# SUBBOARD-aux_supply.net
KiCad netlist of a schematic drawn in Altium Designer
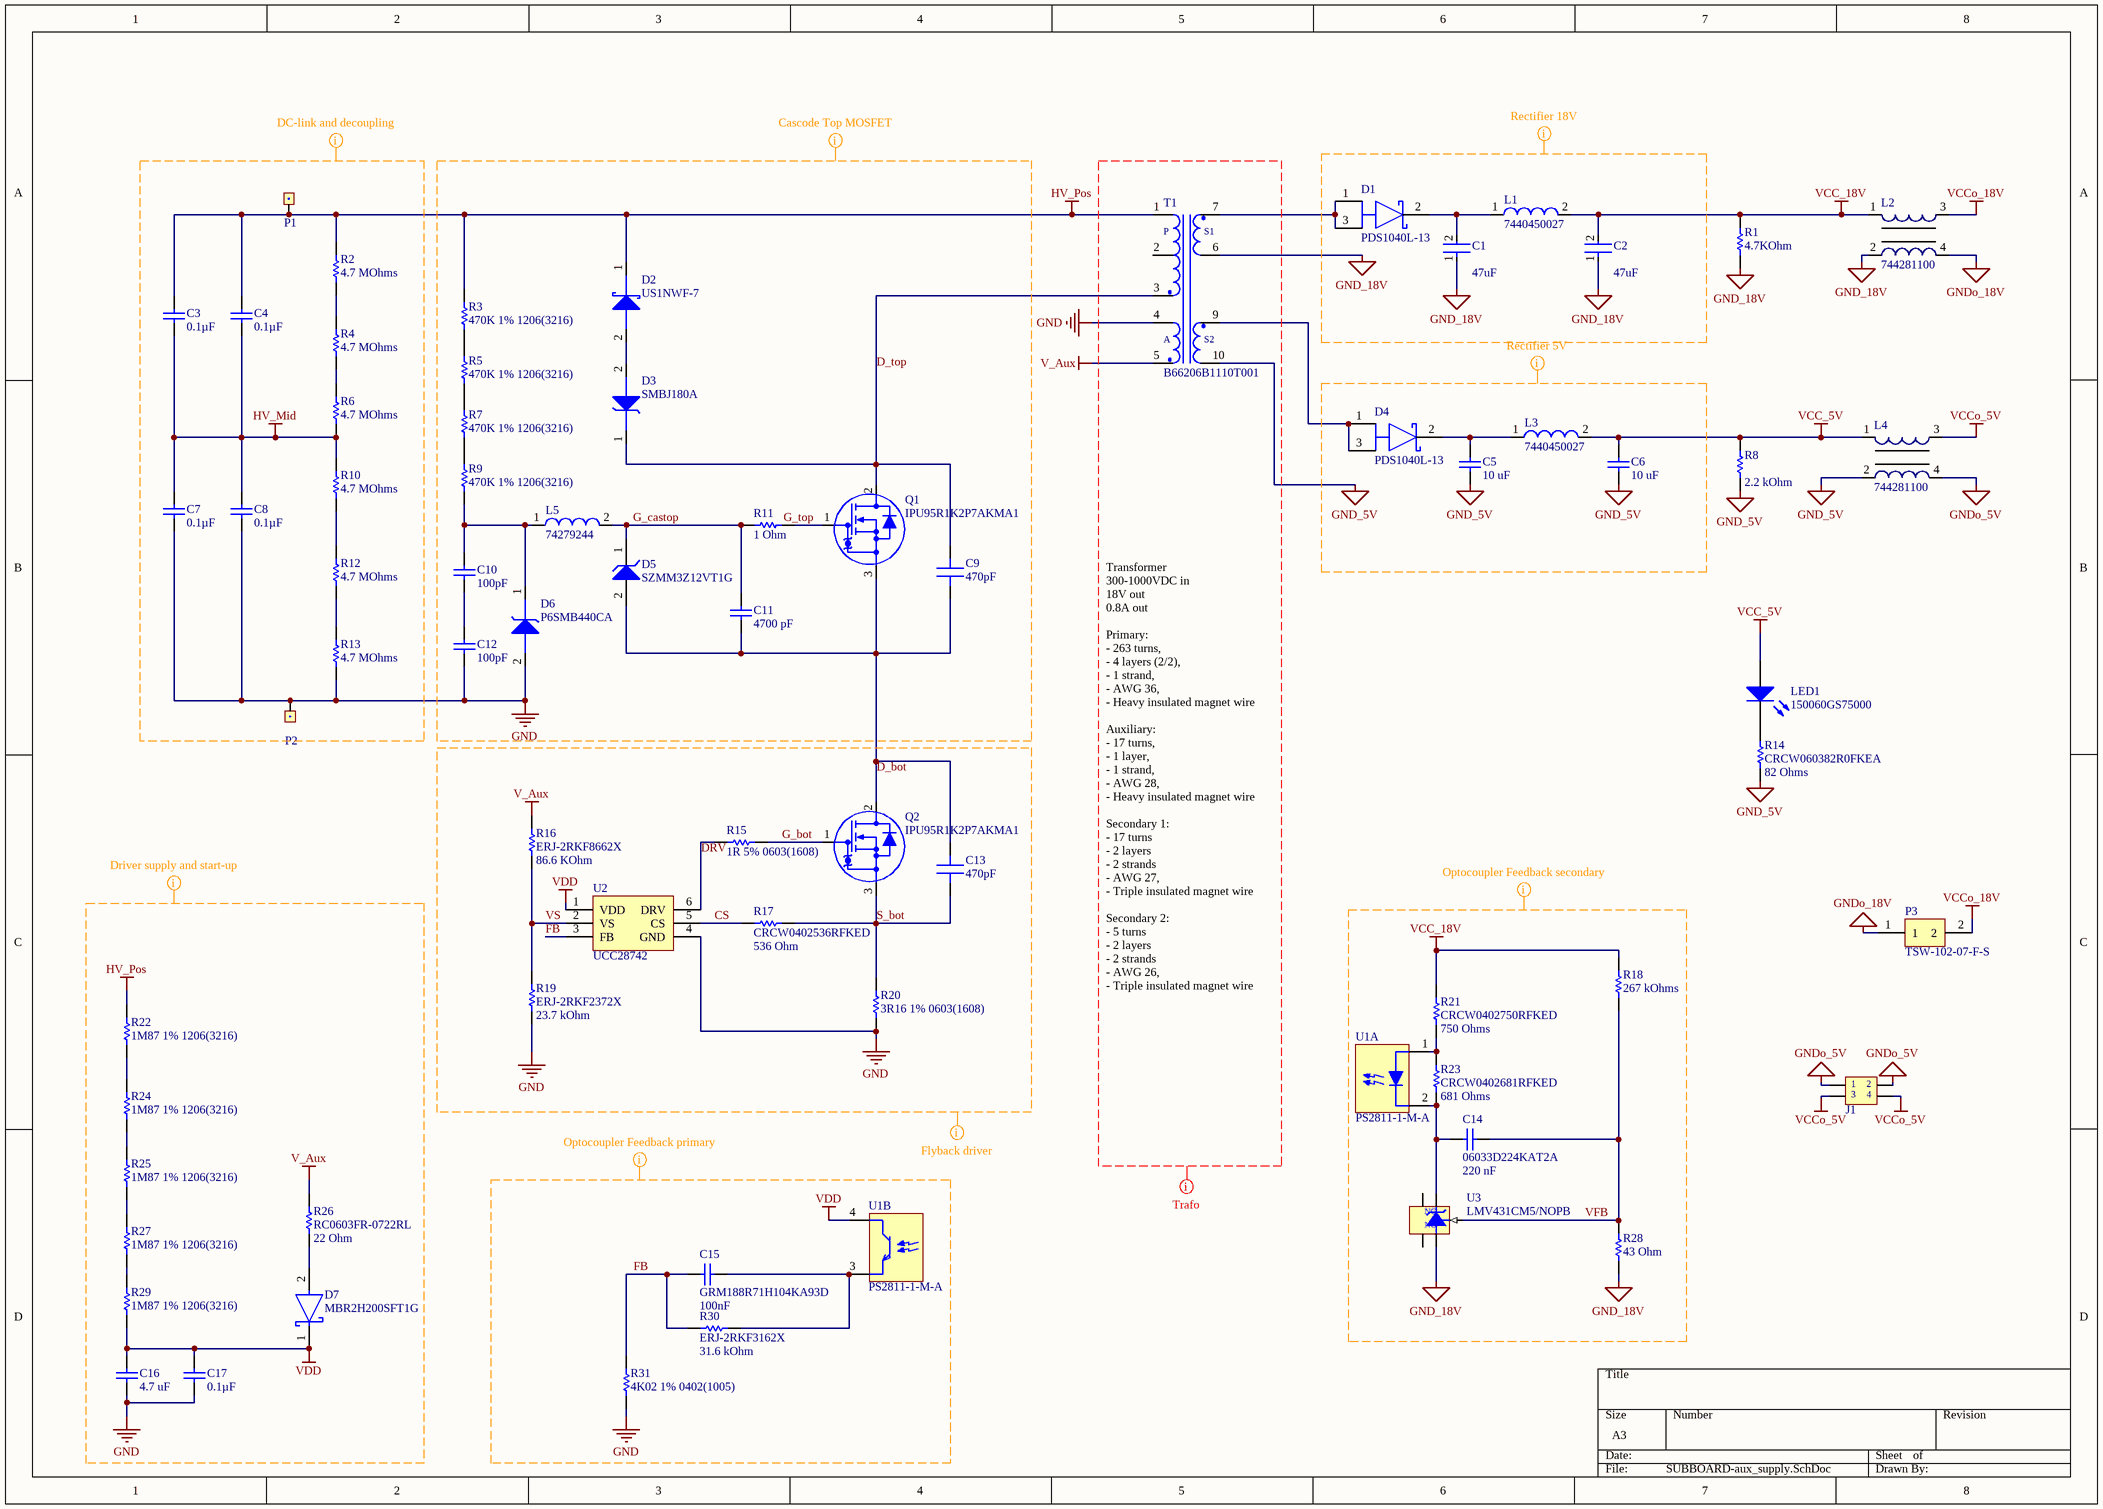
[diagram p0: SUBBOARD-aux_supply.SchDoc]

(export (version "E")
  (design (tool "Eeschema 10.0.6"))
  (components
    (comp (ref "C1")
      (value "47uF")
      (footprint "FP-C3216-160-MFG")
      (description "CAP CER 47UF 25V X5R 1206")
      (fields (field (name "3DS PART NUMBER") "220-00004") (field (name "VOLTAGE") "25V"))
      (libsource (lib "Altium Content Vault") (part "11868f565c42a9108669ba33697ecf6"))
    )
    (comp (ref "C2")
      (value "47uF")
      (footprint "FP-C3216-160-MFG")
      (description "CAP CER 47UF 25V X5R 1206")
      (fields (field (name "3DS PART NUMBER") "220-00004") (field (name "VOLTAGE") "25V"))
      (libsource (lib "Altium Content Vault") (part "11868f565c42a9108669ba33697ecf6"))
    )
    (comp (ref "C3")
      (value "VJ1812Y104KXEAT5Z")
      (footprint "VISH-VJ1812-2_L")
      (fields
        (field (name "MANUFACTURER") "Vishay")
        (field (name "CAPACITANCE") "0.1µF")
        (field (name "TOLERANCE") "±10%")
      )
      (libsource (lib "Altium Content Vault") (part "CAP-NP-2"))
    )
    (comp (ref "C4")
      (value "VJ1812Y104KXEAT5Z")
      (footprint "VISH-VJ1812-2_L")
      (fields
        (field (name "MANUFACTURER") "Vishay")
        (field (name "CAPACITANCE") "0.1µF")
        (field (name "TOLERANCE") "±10%")
      )
      (libsource (lib "Altium Content Vault") (part "CAP-NP-2"))
    )
    (comp (ref "C5")
      (value "10 uF")
      (footprint "CAPC2013X140X45NL15T25")
      (fields (field (name "PART NUMBER") "GRM21BR71A106KE51L") (field (name "MANUFACTURER") "Murata"))
      (libsource (lib "Altium Content Vault") (part "CAP"))
    )
    (comp (ref "C6")
      (value "10 uF")
      (footprint "CAPC2013X140X45NL15T25")
      (fields (field (name "PART NUMBER") "GRM21BR71A106KE51L") (field (name "MANUFACTURER") "Murata"))
      (libsource (lib "Altium Content Vault") (part "CAP"))
    )
    (comp (ref "C7")
      (value "VJ1812Y104KXEAT5Z")
      (footprint "VISH-VJ1812-2_L")
      (fields
        (field (name "MANUFACTURER") "Vishay")
        (field (name "CAPACITANCE") "0.1µF")
        (field (name "TOLERANCE") "±10%")
      )
      (libsource (lib "Altium Content Vault") (part "CAP-NP-2"))
    )
    (comp (ref "C8")
      (value "VJ1812Y104KXEAT5Z")
      (footprint "VISH-VJ1812-2_L")
      (fields
        (field (name "MANUFACTURER") "Vishay")
        (field (name "CAPACITANCE") "0.1µF")
        (field (name "TOLERANCE") "±10%")
      )
      (libsource (lib "Altium Content Vault") (part "CAP-NP-2"))
    )
    (comp (ref "C9")
      (value "C4520X7R3A471K130KA")
      (footprint "CAPC1808(4520)215_L")
      (description "CAP CER 470PF 1KV X7R 1808")
      (fields
        (field (name "MANUFACTURER") "TDK")
        (field (name "CAPACITANCE") "470pF")
        (field (name "TOLERANCE") "10%")
      )
      (libsource (lib "Altium_Library_POWERLAB") (part "C4520X7R3A471K130KA"))
    )
    (comp (ref "C10")
      (value "100pF")
      (footprint "CAPC1206(3216)170_L")
      (description "CAP 100pF 500V ±2% 1206 (3216 Metric) Thickness 1.7mm SMD")
      (fields (field (name "TOLERANCE") "Â±2%") (field (name "Comment") "CAP 100pF 500V 1206(3216)"))
      (libsource (lib "Altium Content Vault") (part "CAP"))
    )
    (comp (ref "C11")
      (value "C0805C472J5RACTU")
      (footprint "CAPC2013X110X50LL20T25")
      (fields (field (name "MANUFACTURER") "Kemet") (field (name "CAPACITANCE") "4700 pF"))
      (libsource (lib "Altium Content Vault") (part "CAP"))
    )
    (comp (ref "C12")
      (value "100pF")
      (footprint "CAPC1206(3216)170_L")
      (description "CAP 100pF 500V ±2% 1206 (3216 Metric) Thickness 1.7mm SMD")
      (fields (field (name "TOLERANCE") "Â±2%") (field (name "Comment") "CAP 100pF 500V 1206(3216)"))
      (libsource (lib "Altium Content Vault") (part "CAP"))
    )
    (comp (ref "C13")
      (value "C4520X7R3A471K130KA")
      (footprint "CAPC1808(4520)215_L")
      (description "CAP CER 470PF 1KV X7R 1808")
      (fields
        (field (name "MANUFACTURER") "TDK")
        (field (name "CAPACITANCE") "470pF")
        (field (name "TOLERANCE") "10%")
      )
      (libsource (lib "Altium_Library_POWERLAB") (part "C4520X7R3A471K130KA"))
    )
    (comp (ref "C14")
      (value "06033D224KAT2A")
      (footprint "CAPC1608X90X35NL15T15")
      (fields (field (name "MANUFACTURER") "AVX Interconnect / Elco") (field (name "CAPACITANCE") "220 nF"))
      (libsource (lib "Altium Content Vault") (part "CAP"))
    )
    (comp (ref "C15")
      (value "GRM188R71H104KA93D")
      (footprint "CAPC1608X90X35LL10T15")
      (description "Chip Capacitor, 0.1 uF, +/- 10%, 50 V, -55 to 125 degC, 0603 (1608 Metric), RoHS, Tape and Reel")
      (fields
        (field (name "TOLERANCE") "10%")
        (field (name "CAPACITANCE") "100nF")
        (field (name "VOLTAGE") "50V")
      )
      (libsource (lib "Altium Content Vault") (part "CAP-NP-2"))
    )
    (comp (ref "C16")
      (value "GRM219R6YA475MA73D")
      (footprint "CAPC2013X95X45NL15T25")
      (fields (field (name "MANUFACTURER") "Murata") (field (name "CAPACITANCE") "4.7 uF"))
      (libsource (lib "Altium Content Vault") (part "CAP"))
    )
    (comp (ref "C17")
      (value "CL10B104KB8NNNC")
      (footprint "SAMS-C0603-2_L")
      (description "Multi-layer Ceramic Capacitor, -55 to 125 degC, 2-Pin SMD (0603), RoHS, Tape and Reel")
      (fields (field (name "CAPACITANCE") "0.1µF") (field (name "MANUFACTURER") "Samsung Electro-Mechanics"))
      (libsource (lib "Altium Content Vault") (part "CAP-NP-2"))
    )
    (comp (ref "D1")
      (value "PDS1040L-13")
      (footprint "FP-PowerDI5-MFG")
      (description "DIODE SCHOTTKY 40V 10A POWERDI5")
      (fields
        (field (name "OCTOPART") "https://octopart.com/pds1040l-13-diodes+inc.-332540")
        (field (name "MANUFACTURER") "Diodes Inc.")
      )
      (libsource (lib "Altium Content Vault") (part "742f7ab95c42997246ebbe41a6c66ae"))
    )
    (comp (ref "D2")
      (value "US1NWF-7")
      (footprint "SOD123F")
      (description "DIODE GEN PURP 1.2KV 1A SOD123F")
      (fields (field (name "MANUFACTURER") "Diodes"))
      (libsource (lib "Altium_Library_POWERLAB") (part "US1NWF-7"))
    )
    (comp (ref "D3")
      (value "SMBJ180A")
      (footprint "DO-214AA SMB")
      (description "Diode TVS Single Uni-Dir 180V 600W 2-Pin SMB T/R")
      (fields (field (name "MANUFACTURER") "Littelfuse"))
      (libsource (lib "Altium_Library_POWERLAB") (part "SMBJ180A"))
    )
    (comp (ref "D4")
      (value "PDS1040L-13")
      (footprint "FP-PowerDI5-MFG")
      (description "DIODE SCHOTTKY 40V 10A POWERDI5")
      (fields
        (field (name "OCTOPART") "https://octopart.com/pds1040l-13-diodes+inc.-332540")
        (field (name "MANUFACTURER") "Diodes Inc.")
      )
      (libsource (lib "Altium Content Vault") (part "742f7ab95c42997246ebbe41a6c66ae"))
    )
    (comp (ref "D5")
      (value "SZMM3Z12VT1G")
      (footprint "ONSC-SOD-323-2-477-02_V")
      (description "Zener Voltage Regulator, 300 mW, 2-Pin SOD-323, Pb-Free, Tape and Reel")
      (fields (field (name "MANUFACTURER") "On Semiconductor"))
      (libsource (lib "Altium Content Vault") (part "ONSC-K1A2-2"))
    )
    (comp (ref "D6")
      (value "P6SMB440CA")
      (footprint "DO-214AA SMB")
      (description "LITTELFUSE - P6SMB440CA - TVS Diode, P6SMB series, Bidirectional, 376 V, 602 V, DO-214AA, 2 Pins")
      (fields (field (name "MANUFACTURER") "Littelfuse"))
      (libsource (lib "Altium_Library_POWERLAB") (part "P6SMB440CA"))
    )
    (comp (ref "D7")
      (value "MBR2H200SFT1G")
      (footprint "FP-498-MFG")
      (description "DIODE SCHOTTKY 200V 2A SOD123FL")
      (fields
        (field (name "MANUFACTURER") "ON Semiconductor")
        (field (name "OCTOPART") "https://octopart.com/mbr2h200sft1g-on+semiconductor-51167333")
      )
      (libsource (lib "Altium Content Vault") (part "1d6ec82d83fb6aee721767c19dac4b9"))
    )
    (comp (ref "J1")
      (value "SQT-102-01-F-D")
      (footprint "SQT-102-01-F-D")
      (description "Conn Socket Strip SKT 4 POS 2mm Solder ST Thru-Hole")
      (fields (field (name "MANUFACTURER") "Samtec"))
      (libsource (lib "Altium_Library_POWERLAB") (part "SQT-102-01-F-D"))
    )
    (comp (ref "L1")
      (value "7440450027")
      (footprint "WE-LQ-L")
      (description "SMD-RF-Inductor WE-LQ, L = 2.70 µH")
      (libsource (lib "Altium Content Vault") (part "PAS-IND-INDUCTOR-2"))
    )
    (comp (ref "L2")
      (value "744281100")
      (footprint "WE-SCC 7345")
      (description "SMD Common Mode Line Filter WE-SCC, L=10.0 µH")
      (fields (field (name "MANUFACTURER") "Wuerth Elektronik"))
      (libsource (lib "Altium Content Vault") (part "WE-IND-INDUCTOR-4E"))
    )
    (comp (ref "L3")
      (value "7440450027")
      (footprint "WE-LQ-L")
      (description "SMD-RF-Inductor WE-LQ, L = 2.70 µH")
      (libsource (lib "Altium Content Vault") (part "PAS-IND-INDUCTOR-2"))
    )
    (comp (ref "L4")
      (value "744281100")
      (footprint "WE-SCC 7345")
      (description "SMD Common Mode Line Filter WE-SCC, L=10.0 µH")
      (fields (field (name "MANUFACTURER") "Wuerth Elektronik"))
      (libsource (lib "Altium Content Vault") (part "WE-IND-INDUCTOR-4E"))
    )
    (comp (ref "L5")
      (value "74279244")
      (footprint "SMD-1806")
      (description "SMD EMI Suppression Ferrite Bead WE-CBF, Z = 850 Ohm")
      (libsource (lib "Altium Content Vault") (part "PAS-IND-INDUCTOR-2"))
    )
    (comp (ref "LED1")
      (value "150060GS75000")
      (footprint "0603_A")
      (description "SMD mono-color Chip LED, WL-SMCW, Green")
      (fields (field (name "MANUFACTURER") "Wuerth Elektronik"))
      (libsource (lib "Altium Content Vault") (part "WE-LED_K1A2-2"))
    )
    (comp (ref "P1")
      (value "TSW-101-07-F-S")
      (footprint "TSW-101-07-F-S")
      (description "In a Pack of 50, Samtec TSW, 1 Way, 1 Row, Straight PCB Header")
      (fields (field (name "MANUFACTURER") "Samtec"))
      (libsource (lib "") (part "TSW-101-07-F-S_1"))
    )
    (comp (ref "P2")
      (value "TSW-101-07-F-S")
      (footprint "TSW-101-07-F-S")
      (description "In a Pack of 50, Samtec TSW, 1 Way, 1 Row, Straight PCB Header")
      (fields (field (name "MANUFACTURER") "Samtec"))
      (libsource (lib "Altium_Library_POWERLAB") (part "TSW-101-07-F-S"))
    )
    (comp (ref "P3")
      (value "TSW-102-07-F-S")
      (footprint "TSW-102-07-F-S")
      (description "Conn Unshrouded Header HDR 2 POS 2.54mm Solder ST Thru-Hole")
      (fields (field (name "MANUFACTURER") "Samtec"))
      (libsource (lib "Altium_Library_POWERLAB") (part "TSW-102-07-F-S"))
    )
    (comp (ref "Q1")
      (value "IPU95R1K2P7AKMA1")
      (footprint "IPAK")
      (description "Trans MOSFET N-CH 600V 6A 3-Pin(3+Tab) TO-251 Tube")
      (fields (field (name "MANUFACTURER") "Infineon"))
      (libsource (lib "Altium_Library_POWERLAB") (part "IPU95R1K2P7AKMA1"))
    )
    (comp (ref "Q2")
      (value "IPU95R1K2P7AKMA1")
      (footprint "IPAK")
      (description "Trans MOSFET N-CH 600V 6A 3-Pin(3+Tab) TO-251 Tube")
      (fields (field (name "MANUFACTURER") "Infineon"))
      (libsource (lib "Altium_Library_POWERLAB") (part "IPU95R1K2P7AKMA1"))
    )
    (comp (ref "R1")
      (value "CRCW12064K70FKEA")
      (footprint "RESC3216X60X45LL15T20")
      (description "Chip Resistor, 4.7 KOhm, +/- 1%, 0.25 W, -55 to 155 degC, 1206 (3216 Metric), RoHS, Tape and Reel")
      (fields
        (field (name "MANUFACTURER") "Vishay Semiconductor")
        (field (name "RESISTANCE") "4.7KOhm")
        (field (name "TOLERANCE") "1%")
      )
      (libsource (lib "Altium Content Vault") (part "RES-2"))
    )
    (comp (ref "R2")
      (value "4.7 MOhms")
      (footprint "RESC3216X60X45LL10T20")
      (fields (field (name "MANUFACTURER") "Vishay Dale") (field (name "PART NUMBER") "CRCW12064M70FKEA"))
      (libsource (lib "Altium Content Vault") (part "RES"))
    )
    (comp (ref "R3")
      (value "470K 1% 1206(3216)")
      (footprint "RESC1206(3216)_L")
      (description "470K 0.25W 1% 1206 (3216 Metric)  SMD")
      (fields (field (name "TOLERANCE") "1 %") (field (name "POWER") "0.25 W"))
      (libsource (lib "Altium Content Vault") (part "RES"))
    )
    (comp (ref "R4")
      (value "4.7 MOhms")
      (footprint "RESC3216X60X45LL10T20")
      (fields (field (name "MANUFACTURER") "Vishay Dale") (field (name "PART NUMBER") "CRCW12064M70FKEA"))
      (libsource (lib "Altium Content Vault") (part "RES"))
    )
    (comp (ref "R5")
      (value "470K 1% 1206(3216)")
      (footprint "RESC1206(3216)_L")
      (description "470K 0.25W 1% 1206 (3216 Metric)  SMD")
      (fields (field (name "TOLERANCE") "1 %") (field (name "POWER") "0.25 W"))
      (libsource (lib "Altium Content Vault") (part "RES"))
    )
    (comp (ref "R6")
      (value "4.7 MOhms")
      (footprint "RESC3216X60X45LL10T20")
      (fields (field (name "MANUFACTURER") "Vishay Dale") (field (name "PART NUMBER") "CRCW12064M70FKEA"))
      (libsource (lib "Altium Content Vault") (part "RES"))
    )
    (comp (ref "R7")
      (value "470K 1% 1206(3216)")
      (footprint "RESC1206(3216)_L")
      (description "470K 0.25W 1% 1206 (3216 Metric)  SMD")
      (fields (field (name "TOLERANCE") "1 %") (field (name "POWER") "0.25 W"))
      (libsource (lib "Altium Content Vault") (part "RES"))
    )
    (comp (ref "R8")
      (value "2.2 kOhm")
      (footprint "RESC3216X60X45LL10T20")
      (fields (field (name "MANUFACTURER") "Vishay Dale") (field (name "PART NUMBER") "CRCW12062K20FKEA"))
      (libsource (lib "Altium Content Vault") (part "RES"))
    )
    (comp (ref "R9")
      (value "470K 1% 1206(3216)")
      (footprint "RESC1206(3216)_L")
      (description "470K 0.25W 1% 1206 (3216 Metric)  SMD")
      (fields (field (name "TOLERANCE") "1 %") (field (name "POWER") "0.25 W"))
      (libsource (lib "Altium Content Vault") (part "RES"))
    )
    (comp (ref "R10")
      (value "4.7 MOhms")
      (footprint "RESC3216X60X45LL10T20")
      (fields (field (name "MANUFACTURER") "Vishay Dale") (field (name "PART NUMBER") "CRCW12064M70FKEA"))
      (libsource (lib "Altium Content Vault") (part "RES"))
    )
    (comp (ref "R11")
      (value "1 Ohm")
      (footprint "RESC0603(1608)_L")
      (description "1R 0.1W 5% 0603 (1608 Metric)  SMD")
      (fields (field (name "POWER") "0.1 W") (field (name "TOLERANCE") "5 %"))
      (libsource (lib "Altium Content Vault") (part "RES"))
    )
    (comp (ref "R12")
      (value "4.7 MOhms")
      (footprint "RESC3216X60X45LL10T20")
      (fields (field (name "MANUFACTURER") "Vishay Dale") (field (name "PART NUMBER") "CRCW12064M70FKEA"))
      (libsource (lib "Altium Content Vault") (part "RES"))
    )
    (comp (ref "R13")
      (value "4.7 MOhms")
      (footprint "RESC3216X60X45LL10T20")
      (fields (field (name "MANUFACTURER") "Vishay Dale") (field (name "PART NUMBER") "CRCW12064M70FKEA"))
      (libsource (lib "Altium Content Vault") (part "RES"))
    )
    (comp (ref "R14")
      (value "CRCW060382R0FKEA")
      (footprint "RESC1609X50X30LL10T20")
      (fields (field (name "MANUFACTURER") "Vishay Dale") (field (name "ALTIUM_VALUE") "82 Ohms"))
      (libsource (lib "Altium Content Vault") (part "RES"))
    )
    (comp (ref "R15")
      (value "1R 5% 0603(1608)")
      (footprint "RESC0603(1608)_L")
      (description "1R 0.1W 5% 0603 (1608 Metric)  SMD")
      (fields (field (name "POWER") "0.1 W") (field (name "TOLERANCE") "5 %"))
      (libsource (lib "Altium Content Vault") (part "RES"))
    )
    (comp (ref "R16")
      (value "ERJ-2RKF8662X")
      (footprint "RESC1005X40X25ML05T05")
      (description "Chip Resistor, 86.6 KOhm, +/- 1%, 100 mW, -55 to 155 degC, 0402 (1005 Metric), RoHS, Tape and Reel")
      (fields
        (field (name "TOLERANCE") "1%")
        (field (name "RESISTANCE") "86.6 KOhm")
        (field (name "MANUFACTURER") "Basic Passives")
      )
      (libsource (lib "Altium Content Vault") (part "RES-2"))
    )
    (comp (ref "R17")
      (value "CRCW0402536RFKED")
      (footprint "RESC1005X40X25ML05T05")
      (fields (field (name "MANUFACTURER") "Vishay Dale") (field (name "RESISTANCE") "536 Ohm"))
      (libsource (lib "Altium Content Vault") (part "RES"))
    )
    (comp (ref "R18")
      (value "CRCW0402267KFKED")
      (footprint "RESC1005X40X25NL05T05")
      (fields (field (name "MANUFACTURER") "Vishay Dale") (field (name "RESISTANCE") "267 kOhms"))
      (libsource (lib "Altium Content Vault") (part "RES"))
    )
    (comp (ref "R19")
      (value "ERJ-2RKF2372X")
      (footprint "RESC1005X40X25NL05T05")
      (fields
        (field (name "MANUFACTURER") "Panasonic")
        (field (name "RESISTANCE") "23.7 kOhm")
        (field (name "TOLERANCE") "1%")
      )
      (libsource (lib "Altium Content Vault") (part "RES"))
    )
    (comp (ref "R20")
      (value "3R16 1% 0603(1608)")
      (footprint "RESC0603(1608)_L")
      (description "3R16 0.1W 1% 0603 (1608 Metric)  SMD")
      (fields (field (name "POWER") "0.1 W") (field (name "TOLERANCE") "1 %"))
      (libsource (lib "Altium Content Vault") (part "RES"))
    )
    (comp (ref "R21")
      (value "CRCW0402750RFKED")
      (footprint "RESC1005X40X25NL05T05")
      (fields (field (name "MANUFACTURER") "Vishay Dale") (field (name "RESISTANCE") "750 Ohms"))
      (libsource (lib "Altium Content Vault") (part "RES"))
    )
    (comp (ref "R22")
      (value "1M87 1% 1206(3216)")
      (footprint "RESC1206(3216)_L")
      (description "1M87 0.25W 1% 1206 (3216 Metric)  SMD")
      (fields (field (name "POWER") "0.25 W") (field (name "TOLERANCE") "1 %"))
      (libsource (lib "Altium Content Vault") (part "RES"))
    )
    (comp (ref "R23")
      (value "CRCW0402681RFKED")
      (footprint "RESC1005X40X25LL05T05")
      (fields (field (name "MANUFACTURER") "Vishay Dale") (field (name "RESISTANCE") "681 Ohms"))
      (libsource (lib "Altium Content Vault") (part "RES"))
    )
    (comp (ref "R24")
      (value "1M87 1% 1206(3216)")
      (footprint "RESC1206(3216)_L")
      (description "1M87 0.25W 1% 1206 (3216 Metric)  SMD")
      (fields (field (name "POWER") "0.25 W") (field (name "TOLERANCE") "1 %"))
      (libsource (lib "Altium Content Vault") (part "RES"))
    )
    (comp (ref "R25")
      (value "1M87 1% 1206(3216)")
      (footprint "RESC1206(3216)_L")
      (description "1M87 0.25W 1% 1206 (3216 Metric)  SMD")
      (fields (field (name "POWER") "0.25 W") (field (name "TOLERANCE") "1 %"))
      (libsource (lib "Altium Content Vault") (part "RES"))
    )
    (comp (ref "R26")
      (value "RC0603FR-0722RL")
      (footprint "RESC1608X55X25NL10T15")
      (description "Chip Resistor, 22 Ohm, +/- 1%, 0.1 W, -55 to 155 degC, 0603 (1608 Metric), RoHS, Tape and Reel")
      (fields (field (name "RESISTANCE") "22 Ohm"))
      (libsource (lib "Altium Content Vault") (part "RES-2"))
    )
    (comp (ref "R27")
      (value "1M87 1% 1206(3216)")
      (footprint "RESC1206(3216)_L")
      (description "1M87 0.25W 1% 1206 (3216 Metric)  SMD")
      (fields (field (name "POWER") "0.25 W") (field (name "TOLERANCE") "1 %"))
      (libsource (lib "Altium Content Vault") (part "RES"))
    )
    (comp (ref "R28")
      (value "ERJ-2GEJ430X")
      (footprint "RESC1005X40X25ML05T05")
      (fields (field (name "MANUFACTURER") "Panasonic") (field (name "RESISTANCE") "43 Ohm"))
      (libsource (lib "Altium Content Vault") (part "RES"))
    )
    (comp (ref "R29")
      (value "1M87 1% 1206(3216)")
      (footprint "RESC1206(3216)_L")
      (description "1M87 0.25W 1% 1206 (3216 Metric)  SMD")
      (fields (field (name "POWER") "0.25 W") (field (name "TOLERANCE") "1 %"))
      (libsource (lib "Altium Content Vault") (part "RES"))
    )
    (comp (ref "R30")
      (value "ERJ-2RKF3162X")
      (footprint "RESC1005X40X25NL05T05")
      (fields
        (field (name "MANUFACTURER") "Panasonic")
        (field (name "RESISTANCE") "31.6 kOhm")
        (field (name "TOLERANCE") "1%")
      )
      (libsource (lib "Altium Content Vault") (part "RES"))
    )
    (comp (ref "R31")
      (value "4K02 1% 0402(1005)")
      (footprint "RESC0402(1005)_N")
      (description "4K02 0.063W 1% 0402 (1005 Metric)  SMD")
      (fields (field (name "TOLERANCE") "1 %") (field (name "POWER") "0.063 W"))
      (libsource (lib "Altium Content Vault") (part "RES"))
    )
    (comp (ref "T1")
      (value "B66206B1110T001")
      (footprint "B66206B1110T001")
      (description "Flyback transformer 1 primary, 1 auxiliary, 2 secondary, E 20/10/6 (EF 20) Horizontal")
      (libsource (lib "Altium_Library_POWERLAB") (part "B66206B1110T001"))
    )
    (comp (ref "U1")
      (value "PS2811-1-M-A")
      (footprint "SOP127P700X210-4L")
      (description "Transistor Output Optocouplers Hi CTR Opto 1-Ch")
      (libsource (lib "") (part "PS2811-1-M-A_1"))
    )
    (comp (ref "U2")
      (value "UCC28742")
      (footprint "SOT95P280X145-6L")
      (description "High-Efficiency Flyback Controller with Optocoupler Feedback - Texas Instruments")
      (libsource (lib "Altium_Library_POWERLAB") (part "UCC28742"))
    )
    (comp (ref "U3")
      (value "LMV431CM5/NOPB")
      (footprint "DBV0005A_L")
      (description "Low-Voltage (1.24V) Adjustable Precision Shunt Regulators, 5-pin SOT-23, Pb-Free")
      (fields (field (name "MANUFACTURER") "Texas Instruments"))
      (libsource (lib "Altium Content Vault") (part "PM-REG-LMV431-5"))
    )
  )
  (nets
    (net (code "1") (name "/CS") (class "Default")
      (node (ref "R17") (pin "2") (pinfunction "2_2") (pintype "passive"))
      (node (ref "U2") (pin "5") (pinfunction "CS_5") (pintype "power_in"))
    )
    (net (code "2") (name "/DRV") (class "Default")
      (node (ref "R15") (pin "1") (pinfunction "1_1") (pintype "passive"))
      (node (ref "U2") (pin "6") (pinfunction "DRV_6") (pintype "power_in"))
    )
    (net (code "3") (name "/D_bot") (class "Default")
      (node (ref "C11") (pin "1") (pinfunction "1_1") (pintype "passive"))
      (node (ref "C13") (pin "2") (pinfunction "2_2") (pintype "passive"))
      (node (ref "C9") (pin "1") (pinfunction "1_1") (pintype "passive"))
      (node (ref "D5") (pin "2") (pinfunction "A_2") (pintype "passive"))
      (node (ref "Q1") (pin "3") (pinfunction "S_3") (pintype "passive"))
      (node (ref "Q2") (pin "2") (pinfunction "D_2") (pintype "passive"))
    )
    (net (code "4") (name "/D_top") (class "Default")
      (node (ref "C9") (pin "2") (pinfunction "2_2") (pintype "passive"))
      (node (ref "D3") (pin "1") (pinfunction "Cathode_1") (pintype "passive"))
      (node (ref "Q1") (pin "2") (pinfunction "D_2") (pintype "passive"))
      (node (ref "T1") (pin "3") (pinfunction "3_3") (pintype "passive"))
    )
    (net (code "5") (name "/FB") (class "Default")
      (node (ref "C15") (pin "2") (pinfunction "2_2") (pintype "passive"))
      (node (ref "R30") (pin "2") (pinfunction "2_2") (pintype "passive"))
      (node (ref "R31") (pin "2") (pinfunction "2_2") (pintype "passive"))
      (node (ref "U2") (pin "3") (pinfunction "FB_3") (pintype "power_in"))
    )
    (net (code "6") (name "/G_bot") (class "Default")
      (node (ref "Q2") (pin "1") (pinfunction "G_1") (pintype "passive"))
      (node (ref "R15") (pin "2") (pinfunction "2_2") (pintype "passive"))
    )
    (net (code "7") (name "/G_castop") (class "Default")
      (node (ref "C11") (pin "2") (pinfunction "2_2") (pintype "passive"))
      (node (ref "D5") (pin "1") (pinfunction "K_1") (pintype "passive"))
      (node (ref "L5") (pin "2") (pinfunction "2_2") (pintype "passive"))
      (node (ref "R11") (pin "2") (pinfunction "2_2") (pintype "passive"))
    )
    (net (code "8") (name "/G_top") (class "Default")
      (node (ref "Q1") (pin "1") (pinfunction "G_1") (pintype "passive"))
      (node (ref "R11") (pin "1") (pinfunction "1_1") (pintype "passive"))
    )
    (net (code "9") (name "/S_bot") (class "Default")
      (node (ref "C13") (pin "1") (pinfunction "1_1") (pintype "passive"))
      (node (ref "Q2") (pin "3") (pinfunction "S_3") (pintype "passive"))
      (node (ref "R17") (pin "1") (pinfunction "1_1") (pintype "passive"))
      (node (ref "R20") (pin "2") (pinfunction "2_2") (pintype "passive"))
    )
    (net (code "10") (name "/VFB") (class "Default")
      (node (ref "C14") (pin "1") (pinfunction "1_1") (pintype "passive"))
      (node (ref "R18") (pin "2") (pinfunction "2_2") (pintype "passive"))
      (node (ref "R28") (pin "1") (pinfunction "1_1") (pintype "passive"))
      (node (ref "U3") (pin "4") (pinfunction "REF_4") (pintype "input"))
    )
    (net (code "11") (name "/VS") (class "Default")
      (node (ref "R16") (pin "2") (pinfunction "2_2") (pintype "passive"))
      (node (ref "R19") (pin "1") (pinfunction "1_1") (pintype "passive"))
      (node (ref "U2") (pin "2") (pinfunction "VS_2") (pintype "power_in"))
    )
    (net (code "12") (name "GND") (class "Default")
      (node (ref "C12") (pin "1") (pinfunction "1_1") (pintype "passive"))
      (node (ref "C16") (pin "1") (pinfunction "1_1") (pintype "passive"))
      (node (ref "C17") (pin "2") (pinfunction "2_2") (pintype "passive"))
      (node (ref "C7") (pin "2") (pinfunction "2_2") (pintype "passive"))
      (node (ref "C8") (pin "2") (pinfunction "2_2") (pintype "passive"))
      (node (ref "D6") (pin "2") (pinfunction "Anode_2") (pintype "passive"))
      (node (ref "P2") (pin "1") (pinfunction "1_1") (pintype "passive"))
      (node (ref "R13") (pin "1") (pinfunction "1_1") (pintype "passive"))
      (node (ref "R19") (pin "2") (pinfunction "2_2") (pintype "passive"))
      (node (ref "R20") (pin "1") (pinfunction "1_1") (pintype "passive"))
      (node (ref "R31") (pin "1") (pinfunction "1_1") (pintype "passive"))
      (node (ref "T1") (pin "4") (pinfunction "4_4") (pintype "passive"))
      (node (ref "U2") (pin "4") (pinfunction "GND_4") (pintype "power_in"))
    )
    (net (code "13") (name "GND_5V") (class "Default")
      (node (ref "C5") (pin "1") (pinfunction "1_1") (pintype "passive"))
      (node (ref "C6") (pin "1") (pinfunction "1_1") (pintype "passive"))
      (node (ref "L4") (pin "2") (pinfunction "2_2") (pintype "passive"))
      (node (ref "R14") (pin "2") (pinfunction "2_2") (pintype "passive"))
      (node (ref "R8") (pin "2") (pinfunction "2_2") (pintype "passive"))
      (node (ref "T1") (pin "10") (pinfunction "10_10") (pintype "passive"))
    )
    (net (code "14") (name "GND_18V") (class "Default")
      (node (ref "C1") (pin "1") (pinfunction "1_1") (pintype "passive"))
      (node (ref "C2") (pin "1") (pinfunction "1_1") (pintype "passive"))
      (node (ref "L2") (pin "2") (pinfunction "2_2") (pintype "passive"))
      (node (ref "R1") (pin "2") (pinfunction "2_2") (pintype "passive"))
      (node (ref "R28") (pin "2") (pinfunction "2_2") (pintype "passive"))
      (node (ref "T1") (pin "6") (pinfunction "6_6") (pintype "passive"))
      (node (ref "U3") (pin "5") (pinfunction "A_5") (pintype "passive"))
    )
    (net (code "15") (name "GNDo_5V") (class "Default")
      (node (ref "J1") (pin "1") (pinfunction "1_1") (pintype "passive"))
      (node (ref "J1") (pin "2") (pinfunction "2_2") (pintype "passive"))
      (node (ref "L4") (pin "4") (pinfunction "4_4") (pintype "passive"))
    )
    (net (code "16") (name "GNDo_18V") (class "Default")
      (node (ref "L2") (pin "4") (pinfunction "4_4") (pintype "passive"))
      (node (ref "P3") (pin "1") (pinfunction "1_1") (pintype "passive"))
    )
    (net (code "17") (name "HV_Mid") (class "Default")
      (node (ref "C3") (pin "2") (pinfunction "2_2") (pintype "passive"))
      (node (ref "C4") (pin "2") (pinfunction "2_2") (pintype "passive"))
      (node (ref "C7") (pin "1") (pinfunction "1_1") (pintype "passive"))
      (node (ref "C8") (pin "1") (pinfunction "1_1") (pintype "passive"))
      (node (ref "R10") (pin "2") (pinfunction "2_2") (pintype "passive"))
      (node (ref "R6") (pin "1") (pinfunction "1_1") (pintype "passive"))
    )
    (net (code "18") (name "HV_Pos") (class "Default")
      (node (ref "C3") (pin "1") (pinfunction "1_1") (pintype "passive"))
      (node (ref "C4") (pin "1") (pinfunction "1_1") (pintype "passive"))
      (node (ref "D2") (pin "1") (pinfunction "Cathode_1") (pintype "passive"))
      (node (ref "P1") (pin "1") (pinfunction "1_1") (pintype "passive"))
      (node (ref "R2") (pin "2") (pinfunction "2_2") (pintype "passive"))
      (node (ref "R22") (pin "2") (pinfunction "2_2") (pintype "passive"))
      (node (ref "R3") (pin "2") (pinfunction "2_2") (pintype "passive"))
      (node (ref "T1") (pin "1") (pinfunction "1_1") (pintype "passive"))
    )
    (net (code "19") (name "Net-(C10-Pad1)") (class "Default")
      (node (ref "C10") (pin "1") (pinfunction "1_1") (pintype "passive"))
      (node (ref "C12") (pin "2") (pinfunction "2_2") (pintype "passive"))
    )
    (net (code "20") (name "Net-(C15-Pad1)") (class "Default")
      (node (ref "C15") (pin "1") (pinfunction "1_1") (pintype "passive"))
      (node (ref "R30") (pin "1") (pinfunction "1_1") (pintype "passive"))
      (node (ref "U1") (pin "3") (pinfunction "3_3") (pintype "passive"))
    )
    (net (code "21") (name "Net-(D1-A-Pad1)") (class "Default")
      (node (ref "D1") (pin "1") (pinfunction "A_1") (pintype "passive"))
      (node (ref "D1") (pin "3") (pinfunction "A_3") (pintype "passive"))
      (node (ref "T1") (pin "7") (pinfunction "7_7") (pintype "passive"))
    )
    (net (code "22") (name "Net-(D1-C)") (class "Default")
      (node (ref "C1") (pin "2") (pinfunction "2_2") (pintype "passive"))
      (node (ref "D1") (pin "2") (pinfunction "C_2") (pintype "passive"))
      (node (ref "L1") (pin "1") (pinfunction "1_1") (pintype "passive"))
    )
    (net (code "23") (name "Net-(D2-Anode)") (class "Default")
      (node (ref "D2") (pin "2") (pinfunction "Anode_2") (pintype "passive"))
      (node (ref "D3") (pin "2") (pinfunction "Anode_2") (pintype "passive"))
    )
    (net (code "24") (name "Net-(D4-A-Pad1)") (class "Default")
      (node (ref "D4") (pin "1") (pinfunction "A_1") (pintype "passive"))
      (node (ref "D4") (pin "3") (pinfunction "A_3") (pintype "passive"))
      (node (ref "T1") (pin "9") (pinfunction "9_9") (pintype "passive"))
    )
    (net (code "25") (name "Net-(D4-C)") (class "Default")
      (node (ref "C5") (pin "2") (pinfunction "2_2") (pintype "passive"))
      (node (ref "D4") (pin "2") (pinfunction "C_2") (pintype "passive"))
      (node (ref "L3") (pin "1") (pinfunction "1_1") (pintype "passive"))
    )
    (net (code "26") (name "Net-(D6-Cathode)") (class "Default")
      (node (ref "C10") (pin "2") (pinfunction "2_2") (pintype "passive"))
      (node (ref "D6") (pin "1") (pinfunction "Cathode_1") (pintype "passive"))
      (node (ref "L5") (pin "1") (pinfunction "1_1") (pintype "passive"))
      (node (ref "R9") (pin "1") (pinfunction "1_1") (pintype "passive"))
    )
    (net (code "27") (name "Net-(D7-A)") (class "Default")
      (node (ref "D7") (pin "2") (pinfunction "A_2") (pintype "passive"))
      (node (ref "R26") (pin "1") (pinfunction "1_1") (pintype "passive"))
    )
    (net (code "28") (name "Net-(LED1-K)") (class "Default")
      (node (ref "LED1") (pin "1") (pinfunction "K_1") (pintype "passive"))
      (node (ref "R14") (pin "1") (pinfunction "1_1") (pintype "passive"))
    )
    (net (code "29") (name "Net-(R2-Pad1)") (class "Default")
      (node (ref "R2") (pin "1") (pinfunction "1_1") (pintype "passive"))
      (node (ref "R4") (pin "2") (pinfunction "2_2") (pintype "passive"))
    )
    (net (code "30") (name "Net-(R3-Pad1)") (class "Default")
      (node (ref "R3") (pin "1") (pinfunction "1_1") (pintype "passive"))
      (node (ref "R5") (pin "2") (pinfunction "2_2") (pintype "passive"))
    )
    (net (code "31") (name "Net-(R4-Pad1)") (class "Default")
      (node (ref "R4") (pin "1") (pinfunction "1_1") (pintype "passive"))
      (node (ref "R6") (pin "2") (pinfunction "2_2") (pintype "passive"))
    )
    (net (code "32") (name "Net-(R5-Pad1)") (class "Default")
      (node (ref "R5") (pin "1") (pinfunction "1_1") (pintype "passive"))
      (node (ref "R7") (pin "2") (pinfunction "2_2") (pintype "passive"))
    )
    (net (code "33") (name "Net-(R7-Pad1)") (class "Default")
      (node (ref "R7") (pin "1") (pinfunction "1_1") (pintype "passive"))
      (node (ref "R9") (pin "2") (pinfunction "2_2") (pintype "passive"))
    )
    (net (code "34") (name "Net-(R10-Pad1)") (class "Default")
      (node (ref "R10") (pin "1") (pinfunction "1_1") (pintype "passive"))
      (node (ref "R12") (pin "2") (pinfunction "2_2") (pintype "passive"))
    )
    (net (code "35") (name "Net-(R12-Pad1)") (class "Default")
      (node (ref "R12") (pin "1") (pinfunction "1_1") (pintype "passive"))
      (node (ref "R13") (pin "2") (pinfunction "2_2") (pintype "passive"))
    )
    (net (code "36") (name "Net-(R21-Pad2)") (class "Default")
      (node (ref "R21") (pin "2") (pinfunction "2_2") (pintype "passive"))
      (node (ref "R23") (pin "1") (pinfunction "1_1") (pintype "passive"))
      (node (ref "U1") (pin "1") (pinfunction "1_1") (pintype "passive"))
    )
    (net (code "37") (name "Net-(R22-Pad1)") (class "Default")
      (node (ref "R22") (pin "1") (pinfunction "1_1") (pintype "passive"))
      (node (ref "R24") (pin "2") (pinfunction "2_2") (pintype "passive"))
    )
    (net (code "38") (name "Net-(R24-Pad1)") (class "Default")
      (node (ref "R24") (pin "1") (pinfunction "1_1") (pintype "passive"))
      (node (ref "R25") (pin "2") (pinfunction "2_2") (pintype "passive"))
    )
    (net (code "39") (name "Net-(R25-Pad1)") (class "Default")
      (node (ref "R25") (pin "1") (pinfunction "1_1") (pintype "passive"))
      (node (ref "R27") (pin "2") (pinfunction "2_2") (pintype "passive"))
    )
    (net (code "40") (name "Net-(R27-Pad1)") (class "Default")
      (node (ref "R27") (pin "1") (pinfunction "1_1") (pintype "passive"))
      (node (ref "R29") (pin "2") (pinfunction "2_2") (pintype "passive"))
    )
    (net (code "41") (name "Net-(U3-K)") (class "Default")
      (node (ref "C14") (pin "2") (pinfunction "2_2") (pintype "passive"))
      (node (ref "R23") (pin "2") (pinfunction "2_2") (pintype "passive"))
      (node (ref "U1") (pin "2") (pinfunction "2_2") (pintype "passive"))
      (node (ref "U3") (pin "3") (pinfunction "K_3") (pintype "passive"))
    )
    (net (code "42") (name "VCC_5V") (class "Default")
      (node (ref "C6") (pin "2") (pinfunction "2_2") (pintype "passive"))
      (node (ref "L3") (pin "2") (pinfunction "2_2") (pintype "passive"))
      (node (ref "L4") (pin "1") (pinfunction "1_1") (pintype "passive"))
      (node (ref "LED1") (pin "2") (pinfunction "A_2") (pintype "passive"))
      (node (ref "R8") (pin "1") (pinfunction "1_1") (pintype "passive"))
    )
    (net (code "43") (name "VCC_18V") (class "Default")
      (node (ref "C2") (pin "2") (pinfunction "2_2") (pintype "passive"))
      (node (ref "L1") (pin "2") (pinfunction "2_2") (pintype "passive"))
      (node (ref "L2") (pin "1") (pinfunction "1_1") (pintype "passive"))
      (node (ref "R1") (pin "1") (pinfunction "1_1") (pintype "passive"))
      (node (ref "R18") (pin "1") (pinfunction "1_1") (pintype "passive"))
      (node (ref "R21") (pin "1") (pinfunction "1_1") (pintype "passive"))
    )
    (net (code "44") (name "VCCo_5V") (class "Default")
      (node (ref "J1") (pin "3") (pinfunction "3_3") (pintype "passive"))
      (node (ref "J1") (pin "4") (pinfunction "4_4") (pintype "passive"))
      (node (ref "L4") (pin "3") (pinfunction "3_3") (pintype "passive"))
    )
    (net (code "45") (name "VCCo_18V") (class "Default")
      (node (ref "L2") (pin "3") (pinfunction "3_3") (pintype "passive"))
      (node (ref "P3") (pin "2") (pinfunction "2_2") (pintype "passive"))
    )
    (net (code "46") (name "VDD") (class "Default")
      (node (ref "C16") (pin "2") (pinfunction "2_2") (pintype "passive"))
      (node (ref "C17") (pin "1") (pinfunction "1_1") (pintype "passive"))
      (node (ref "D7") (pin "1") (pinfunction "C_1") (pintype "passive"))
      (node (ref "R29") (pin "1") (pinfunction "1_1") (pintype "passive"))
      (node (ref "U1") (pin "4") (pinfunction "4_4") (pintype "passive"))
      (node (ref "U2") (pin "1") (pinfunction "VDD_1") (pintype "power_in"))
    )
    (net (code "47") (name "V_Aux") (class "Default")
      (node (ref "R16") (pin "1") (pinfunction "1_1") (pintype "passive"))
      (node (ref "R26") (pin "2") (pinfunction "2_2") (pintype "passive"))
      (node (ref "T1") (pin "5") (pinfunction "5_5") (pintype "passive"))
    )
    (net (code "48") (name "unconnected-(T1-3-Pad2)") (class "Default")
      (node (ref "T1") (pin "2") (pinfunction "3_2") (pintype "passive"))
    )
    (net (code "49") (name "unconnected-(U3-NC-Pad1)") (class "Default")
      (node (ref "U3") (pin "1") (pinfunction "NC_1") (pintype "passive"))
    )
    (net (code "50") (name "unconnected-(U3-NC-Pad2)") (class "Default")
      (node (ref "U3") (pin "2") (pinfunction "NC_2") (pintype "passive"))
    )
  )
)
